# VCO.net
KiCad netlist of a schematic drawn in Altium Designer
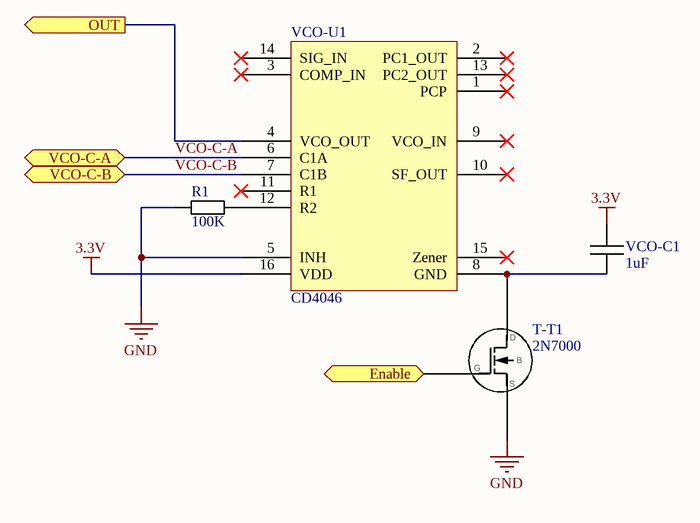
[diagram p0: VCO.SchDoc]

(export (version "E")
  (design (tool "Eeschema 10.0.6"))
  (components
    (comp (ref "R1")
      (value "100K")
      (footprint "R 0805 / 2012")
      (libsource (lib "Standard") (part "Resistor"))
    )
    (comp (ref "T-T1")
      (value "2N7000")
      (footprint "SOT-23-3")
      (description "N-FET")
      (libsource (lib "ICs") (part "2N7000"))
    )
    (comp (ref "VCO-C1")
      (value "1uF")
      (footprint "C 0805 / 2012")
      (libsource (lib "Standard") (part "Capacitor"))
    )
    (comp (ref "VCO-U1")
      (value "CD4046")
      (footprint "SOIC-16")
      (description "PLL / VCO")
      (libsource (lib "ICs") (part "CD4046"))
    )
  )
  (nets
    (net (code "1") (name "/Enable") (class "Default")
      (node (ref "T-T1") (pin "1") (pinfunction "1_1") (pintype "passive"))
    )
    (net (code "2") (name "/OUT") (class "Default")
      (node (ref "VCO-U1") (pin "4") (pinfunction "VCO_OUT_4") (pintype "passive"))
    )
    (net (code "3") (name "/VCO-C-A") (class "Default")
      (node (ref "VCO-U1") (pin "6") (pinfunction "C1A_6") (pintype "passive"))
    )
    (net (code "4") (name "/VCO-C-B") (class "Default")
      (node (ref "VCO-U1") (pin "7") (pinfunction "C1B_7") (pintype "passive"))
    )
    (net (code "5") (name "3.3V") (class "Default")
      (node (ref "VCO-C1") (pin "1") (pinfunction "1_1") (pintype "passive"))
      (node (ref "VCO-U1") (pin "16") (pinfunction "VDD_16") (pintype "passive"))
    )
    (net (code "6") (name "GND") (class "Default")
      (node (ref "R1") (pin "2") (pinfunction "2_2") (pintype "passive"))
      (node (ref "T-T1") (pin "2") (pinfunction "2_2") (pintype "passive"))
      (node (ref "VCO-U1") (pin "5") (pinfunction "INH_5") (pintype "passive"))
    )
    (net (code "7") (name "Net-(VCO-U1-GND)") (class "Default")
      (node (ref "T-T1") (pin "3") (pinfunction "3_3") (pintype "passive"))
      (node (ref "VCO-C1") (pin "2") (pinfunction "1_2") (pintype "passive"))
      (node (ref "VCO-U1") (pin "8") (pinfunction "GND_8") (pintype "passive"))
    )
    (net (code "8") (name "Net-(VCO-U1-R2)") (class "Default")
      (node (ref "R1") (pin "1") (pinfunction "1_1") (pintype "passive"))
      (node (ref "VCO-U1") (pin "12") (pinfunction "R2_12") (pintype "passive"))
    )
    (net (code "9") (name "unconnected-(VCO-U1-COMP_IN-Pad3)") (class "Default")
      (node (ref "VCO-U1") (pin "3") (pinfunction "COMP_IN_3") (pintype "passive+no_connect"))
    )
    (net (code "10") (name "unconnected-(VCO-U1-PC1_OUT-Pad2)") (class "Default")
      (node (ref "VCO-U1") (pin "2") (pinfunction "PC1_OUT_2") (pintype "passive+no_connect"))
    )
    (net (code "11") (name "unconnected-(VCO-U1-PC2_OUT-Pad13)") (class "Default")
      (node (ref "VCO-U1") (pin "13") (pinfunction "PC2_OUT_13") (pintype "passive+no_connect"))
    )
    (net (code "12") (name "unconnected-(VCO-U1-PCP-Pad1)") (class "Default")
      (node (ref "VCO-U1") (pin "1") (pinfunction "PCP_1") (pintype "passive+no_connect"))
    )
    (net (code "13") (name "unconnected-(VCO-U1-R1-Pad11)") (class "Default")
      (node (ref "VCO-U1") (pin "11") (pinfunction "R1_11") (pintype "passive+no_connect"))
    )
    (net (code "14") (name "unconnected-(VCO-U1-SF_OUT-Pad10)") (class "Default")
      (node (ref "VCO-U1") (pin "10") (pinfunction "SF_OUT_10") (pintype "passive+no_connect"))
    )
    (net (code "15") (name "unconnected-(VCO-U1-SIG_IN-Pad14)") (class "Default")
      (node (ref "VCO-U1") (pin "14") (pinfunction "SIG_IN_14") (pintype "passive+no_connect"))
    )
    (net (code "16") (name "unconnected-(VCO-U1-VCO_IN-Pad9)") (class "Default")
      (node (ref "VCO-U1") (pin "9") (pinfunction "VCO_IN_9") (pintype "passive+no_connect"))
    )
    (net (code "17") (name "unconnected-(VCO-U1-Zener-Pad15)") (class "Default")
      (node (ref "VCO-U1") (pin "15") (pinfunction "Zener_15") (pintype "passive+no_connect"))
    )
  )
)
